# Charger.net
KiCad netlist of a schematic drawn in Altium Designer
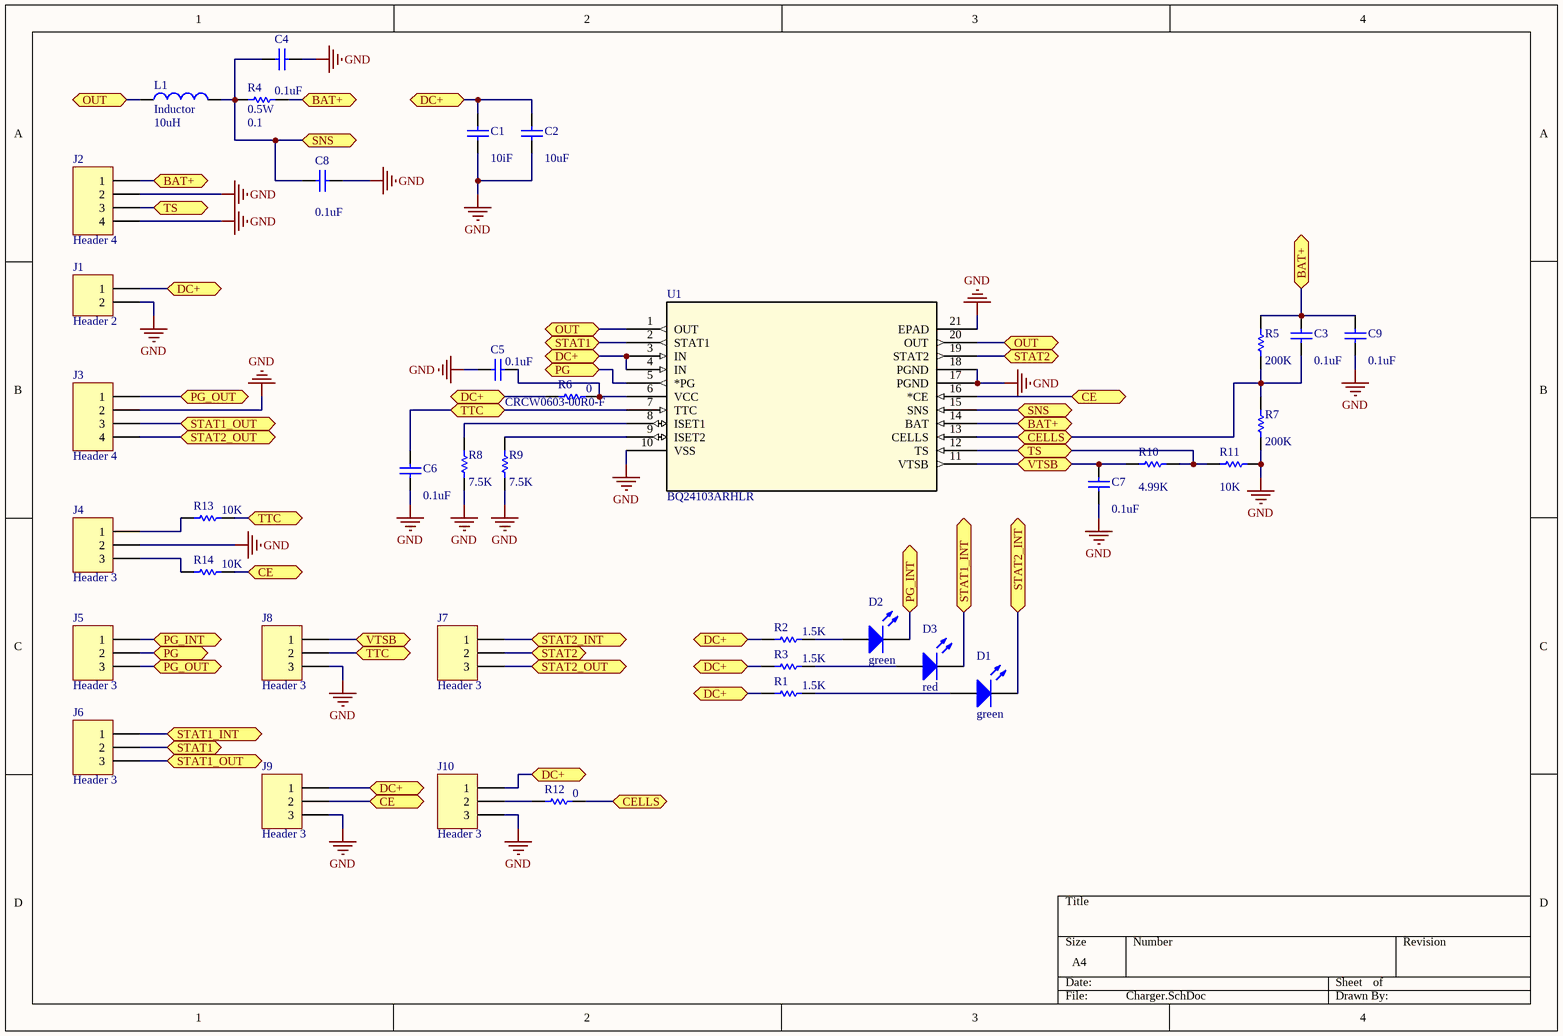
[diagram p0: Charger.SchDoc]

(export (version "E")
  (design (tool "Eeschema 10.0.6"))
  (components
    (comp (ref "C1")
      (value "10iF")
      (footprint "CAPC3216L")
      (description "Capacitor")
      (fields (field (name "PUBLISHER") "Altium Limited"))
      (libsource (lib "Miscellaneous Devices") (part "Cap"))
    )
    (comp (ref "C2")
      (value "10uF")
      (footprint "CAPC3216L")
      (description "Capacitor")
      (fields (field (name "PUBLISHER") "Altium Limited"))
      (libsource (lib "Miscellaneous Devices") (part "Cap"))
    )
    (comp (ref "C3")
      (value "0.1uF")
      (footprint "6-0805_L")
      (description "Capacitor")
      (fields (field (name "PUBLISHER") "Altium Limited"))
      (libsource (lib "Miscellaneous Devices") (part "Cap"))
    )
    (comp (ref "C4")
      (value "0.1uF")
      (footprint "CAPC3216L")
      (description "Capacitor")
      (fields (field (name "PUBLISHER") "Altium Limited"))
      (libsource (lib "Miscellaneous Devices") (part "Cap"))
    )
    (comp (ref "C5")
      (value "0.1uF")
      (footprint "6-0805_L")
      (description "Capacitor")
      (fields (field (name "PUBLISHER") "Altium Limited"))
      (libsource (lib "Miscellaneous Devices") (part "Cap"))
    )
    (comp (ref "C6")
      (value "0.1uF")
      (footprint "6-0805_L")
      (description "Capacitor")
      (fields (field (name "PUBLISHER") "Altium Limited"))
      (libsource (lib "Miscellaneous Devices") (part "Cap"))
    )
    (comp (ref "C7")
      (value "0.1uF")
      (footprint "6-0805_L")
      (description "Capacitor")
      (fields (field (name "PUBLISHER") "Altium Limited"))
      (libsource (lib "Miscellaneous Devices") (part "Cap"))
    )
    (comp (ref "C8")
      (value "0.1uF")
      (footprint "6-0805_L")
      (description "Capacitor")
      (fields (field (name "PUBLISHER") "Altium Limited"))
      (libsource (lib "Miscellaneous Devices") (part "Cap"))
    )
    (comp (ref "C9")
      (value "0.1uF")
      (footprint "CAPC3216L")
      (description "Capacitor")
      (fields (field (name "PUBLISHER") "Altium Limited"))
      (libsource (lib "Miscellaneous Devices") (part "Cap"))
    )
    (comp (ref "D1")
      (value "green")
      (footprint "6-0805_L")
      (description "Typical RED, GREEN, YELLOW, AMBER GaAs LED")
      (fields (field (name "PUBLISHER") "Altium Limited"))
      (libsource (lib "Miscellaneous Devices") (part "LED2"))
    )
    (comp (ref "D2")
      (value "green")
      (footprint "6-0805_L")
      (description "Typical RED, GREEN, YELLOW, AMBER GaAs LED")
      (fields (field (name "PUBLISHER") "Altium Limited"))
      (libsource (lib "Miscellaneous Devices") (part "LED2"))
    )
    (comp (ref "D3")
      (value "red")
      (footprint "6-0805_L")
      (description "Typical RED, GREEN, YELLOW, AMBER GaAs LED")
      (fields (field (name "PUBLISHER") "Altium Limited"))
      (libsource (lib "Miscellaneous Devices") (part "LED2"))
    )
    (comp (ref "J1")
      (value "Header 2")
      (footprint "691305130002")
      (description "Header, 2-Pin")
      (fields (field (name "PUBLISHER") "Altium Limited"))
      (libsource (lib "Miscellaneous Connectors") (part "Header 2"))
    )
    (comp (ref "J2")
      (value "Header 4")
      (footprint "691305130004")
      (description "Header, 4-Pin")
      (fields (field (name "PUBLISHER") "Altium Limited"))
      (libsource (lib "Miscellaneous Connectors") (part "Header 4"))
    )
    (comp (ref "J3")
      (value "Header 4")
      (footprint "691305130004")
      (description "Header, 4-Pin")
      (fields (field (name "PUBLISHER") "Altium Limited"))
      (libsource (lib "Miscellaneous Connectors") (part "Header 4"))
    )
    (comp (ref "J4")
      (value "Header 3")
      (footprint "691305130003")
      (description "Header, 3-Pin")
      (fields (field (name "PUBLISHER") "Altium Limited"))
      (libsource (lib "Miscellaneous Connectors") (part "Header 3"))
    )
    (comp (ref "J5")
      (value "Header 3")
      (footprint "HDR1X3")
      (description "Header, 3-Pin")
      (fields (field (name "PUBLISHER") "Altium Limited"))
      (libsource (lib "Miscellaneous Connectors") (part "Header 3"))
    )
    (comp (ref "J6")
      (value "Header 3")
      (footprint "HDR1X3")
      (description "Header, 3-Pin")
      (fields (field (name "PUBLISHER") "Altium Limited"))
      (libsource (lib "Miscellaneous Connectors") (part "Header 3"))
    )
    (comp (ref "J7")
      (value "Header 3")
      (footprint "HDR1X3")
      (description "Header, 3-Pin")
      (fields (field (name "PUBLISHER") "Altium Limited"))
      (libsource (lib "Miscellaneous Connectors") (part "Header 3"))
    )
    (comp (ref "J8")
      (value "Header 3")
      (footprint "HDR1X3")
      (description "Header, 3-Pin")
      (fields (field (name "PUBLISHER") "Altium Limited"))
      (libsource (lib "Miscellaneous Connectors") (part "Header 3"))
    )
    (comp (ref "J9")
      (value "Header 3")
      (footprint "HDR1X3")
      (description "Header, 3-Pin")
      (fields (field (name "PUBLISHER") "Altium Limited"))
      (libsource (lib "Miscellaneous Connectors") (part "Header 3"))
    )
    (comp (ref "J10")
      (value "Header 3")
      (footprint "HDR1X3")
      (description "Header, 3-Pin")
      (fields (field (name "PUBLISHER") "Altium Limited"))
      (libsource (lib "Miscellaneous Connectors") (part "Header 3"))
    )
    (comp (ref "L1")
      (value "Inductor")
      (footprint "IND2926")
      (fields (field (name "ALTIUM_VALUE") "10uH") (field (name "PUBLISHER") "Altium Limited"))
      (libsource (lib "Miscellaneous Devices") (part "Inductor"))
    )
    (comp (ref "R1")
      (value "1.5K")
      (footprint "6-0805_L")
      (description "Resistor")
      (fields (field (name "PUBLISHER") "Altium Limited"))
      (libsource (lib "Miscellaneous Devices") (part "Res1"))
    )
    (comp (ref "R2")
      (value "1.5K")
      (footprint "6-0805_L")
      (description "Resistor")
      (fields (field (name "PUBLISHER") "Altium Limited"))
      (libsource (lib "Miscellaneous Devices") (part "Res1"))
    )
    (comp (ref "R3")
      (value "1.5K")
      (footprint "6-0805_L")
      (description "Resistor")
      (fields (field (name "PUBLISHER") "Altium Limited"))
      (libsource (lib "Miscellaneous Devices") (part "Res1"))
    )
    (comp (ref "R4")
      (value "0.5W")
      (footprint "12Z-2010")
      (description "Resistor")
      (fields (field (name "ALTIUM_VALUE") "0.1") (field (name "PUBLISHER") "Altium Limited"))
      (libsource (lib "Miscellaneous Devices") (part "Res1"))
    )
    (comp (ref "R5")
      (value "200K")
      (footprint "6-0805_L")
      (description "Resistor")
      (fields (field (name "PUBLISHER") "Altium Limited"))
      (libsource (lib "Miscellaneous Devices") (part "Res1"))
    )
    (comp (ref "R6")
      (value "CRCW0603-00R0-F")
      (footprint "6-0805_L")
      (description "Resistor")
      (fields (field (name "ALTIUM_VALUE") "0") (field (name "PUBLISHER") "Altium Limited"))
      (libsource (lib "Miscellaneous Devices") (part "Res1"))
    )
    (comp (ref "R7")
      (value "200K")
      (footprint "6-0805_L")
      (description "Resistor")
      (fields (field (name "PUBLISHER") "Altium Limited"))
      (libsource (lib "Miscellaneous Devices") (part "Res1"))
    )
    (comp (ref "R8")
      (value "7.5K")
      (footprint "6-0805_L")
      (description "Resistor")
      (fields (field (name "PUBLISHER") "Altium Limited"))
      (libsource (lib "Miscellaneous Devices") (part "Res1"))
    )
    (comp (ref "R9")
      (value "7.5K")
      (footprint "6-0805_L")
      (description "Resistor")
      (fields (field (name "PUBLISHER") "Altium Limited"))
      (libsource (lib "Miscellaneous Devices") (part "Res1"))
    )
    (comp (ref "R10")
      (value "4.99K")
      (footprint "6-0805_L")
      (description "Resistor")
      (fields (field (name "PUBLISHER") "Altium Limited"))
      (libsource (lib "Miscellaneous Devices") (part "Res1"))
    )
    (comp (ref "R11")
      (value "10K")
      (footprint "6-0805_L")
      (description "Resistor")
      (fields (field (name "PUBLISHER") "Altium Limited"))
      (libsource (lib "Miscellaneous Devices") (part "Res1"))
    )
    (comp (ref "R12")
      (value "0")
      (footprint "6-0805_L")
      (description "Resistor")
      (fields (field (name "PUBLISHER") "Altium Limited"))
      (libsource (lib "Miscellaneous Devices") (part "Res1"))
    )
    (comp (ref "R13")
      (value "10K")
      (footprint "6-0805_L")
      (description "Resistor")
      (fields (field (name "PUBLISHER") "Altium Limited"))
      (libsource (lib "Miscellaneous Devices") (part "Res1"))
    )
    (comp (ref "R14")
      (value "10K")
      (footprint "6-0805_L")
      (description "Resistor")
      (fields (field (name "PUBLISHER") "Altium Limited"))
      (libsource (lib "Miscellaneous Devices") (part "Res1"))
    )
    (comp (ref "U1")
      (value "BQ24103ARHLR")
      (footprint "RHL20_2P05X3P05")
      (description "Imported")
      (fields
        (field (name "MANUFACTURER") "Texas Instruments")
        (field (name "GENERIC_PART_NUMBER") "BQ24103A")
        (field (name "COPYRIGHT") "Copyright (C) 2015 Accelerated Designs. All rights reserved")
      )
      (libsource (lib "bq24103") (part "BQ24103ARHLR"))
    )
  )
  (nets
    (net (code "1") (name "/BAT+") (class "Default")
      (node (ref "C3") (pin "1") (pinfunction "1_1") (pintype "passive"))
      (node (ref "C9") (pin "1") (pinfunction "1_1") (pintype "passive"))
      (node (ref "J2") (pin "1") (pinfunction "1_1") (pintype "passive"))
      (node (ref "R4") (pin "2") (pinfunction "2_2") (pintype "passive"))
      (node (ref "R5") (pin "1") (pinfunction "1_1") (pintype "passive"))
      (node (ref "U1") (pin "14") (pinfunction "BAT_14") (pintype "input"))
    )
    (net (code "2") (name "/CE") (class "Default")
      (node (ref "J9") (pin "2") (pinfunction "2_2") (pintype "passive"))
      (node (ref "R14") (pin "2") (pinfunction "2_2") (pintype "passive"))
      (node (ref "U1") (pin "16") (pinfunction "*CE_16") (pintype "input"))
    )
    (net (code "3") (name "/CELLS") (class "Default")
      (node (ref "C3") (pin "2") (pinfunction "2_2") (pintype "passive"))
      (node (ref "R12") (pin "2") (pinfunction "2_2") (pintype "passive"))
      (node (ref "R5") (pin "2") (pinfunction "2_2") (pintype "passive"))
      (node (ref "R7") (pin "1") (pinfunction "1_1") (pintype "passive"))
      (node (ref "U1") (pin "13") (pinfunction "CELLS_13") (pintype "input"))
    )
    (net (code "4") (name "/DC+") (class "Default")
      (node (ref "C1") (pin "2") (pinfunction "2_2") (pintype "passive"))
      (node (ref "C2") (pin "2") (pinfunction "2_2") (pintype "passive"))
      (node (ref "J1") (pin "1") (pinfunction "1_1") (pintype "passive"))
      (node (ref "J10") (pin "1") (pinfunction "1_1") (pintype "passive"))
      (node (ref "J9") (pin "1") (pinfunction "1_1") (pintype "passive"))
      (node (ref "R1") (pin "1") (pinfunction "1_1") (pintype "passive"))
      (node (ref "R2") (pin "1") (pinfunction "1_1") (pintype "passive"))
      (node (ref "R3") (pin "1") (pinfunction "1_1") (pintype "passive"))
      (node (ref "R6") (pin "1") (pinfunction "1_1") (pintype "passive"))
      (node (ref "U1") (pin "3") (pinfunction "IN_3") (pintype "input"))
      (node (ref "U1") (pin "4") (pinfunction "IN_4") (pintype "input"))
    )
    (net (code "5") (name "/OUT") (class "Default")
      (node (ref "L1") (pin "1") (pinfunction "1_1") (pintype "passive"))
      (node (ref "U1") (pin "1") (pinfunction "OUT_1") (pintype "output"))
      (node (ref "U1") (pin "20") (pinfunction "OUT_20") (pintype "output"))
    )
    (net (code "6") (name "/PG") (class "Default")
      (node (ref "J5") (pin "2") (pinfunction "2_2") (pintype "passive"))
      (node (ref "U1") (pin "5") (pinfunction "*PG_5") (pintype "output"))
    )
    (net (code "7") (name "/PG_INT") (class "Default")
      (node (ref "D2") (pin "2") (pinfunction "K_2") (pintype "passive"))
      (node (ref "J5") (pin "1") (pinfunction "1_1") (pintype "passive"))
    )
    (net (code "8") (name "/PG_OUT") (class "Default")
      (node (ref "J3") (pin "1") (pinfunction "1_1") (pintype "passive"))
      (node (ref "J5") (pin "3") (pinfunction "3_3") (pintype "passive"))
    )
    (net (code "9") (name "/SNS") (class "Default")
      (node (ref "C4") (pin "1") (pinfunction "1_1") (pintype "passive"))
      (node (ref "C8") (pin "1") (pinfunction "1_1") (pintype "passive"))
      (node (ref "L1") (pin "2") (pinfunction "2_2") (pintype "passive"))
      (node (ref "R4") (pin "1") (pinfunction "1_1") (pintype "passive"))
      (node (ref "U1") (pin "15") (pinfunction "SNS_15") (pintype "input"))
    )
    (net (code "10") (name "/STAT1") (class "Default")
      (node (ref "J6") (pin "2") (pinfunction "2_2") (pintype "passive"))
      (node (ref "U1") (pin "2") (pinfunction "STAT1_2") (pintype "output"))
    )
    (net (code "11") (name "/STAT1_INT") (class "Default")
      (node (ref "D3") (pin "2") (pinfunction "K_2") (pintype "passive"))
      (node (ref "J6") (pin "1") (pinfunction "1_1") (pintype "passive"))
    )
    (net (code "12") (name "/STAT1_OUT") (class "Default")
      (node (ref "J3") (pin "3") (pinfunction "3_3") (pintype "passive"))
      (node (ref "J6") (pin "3") (pinfunction "3_3") (pintype "passive"))
    )
    (net (code "13") (name "/STAT2") (class "Default")
      (node (ref "J7") (pin "2") (pinfunction "2_2") (pintype "passive"))
      (node (ref "U1") (pin "19") (pinfunction "STAT2_19") (pintype "output"))
    )
    (net (code "14") (name "/STAT2_INT") (class "Default")
      (node (ref "D1") (pin "2") (pinfunction "K_2") (pintype "passive"))
      (node (ref "J7") (pin "1") (pinfunction "1_1") (pintype "passive"))
    )
    (net (code "15") (name "/STAT2_OUT") (class "Default")
      (node (ref "J3") (pin "4") (pinfunction "4_4") (pintype "passive"))
      (node (ref "J7") (pin "3") (pinfunction "3_3") (pintype "passive"))
    )
    (net (code "16") (name "/TS") (class "Default")
      (node (ref "J2") (pin "3") (pinfunction "3_3") (pintype "passive"))
      (node (ref "R10") (pin "1") (pinfunction "1_1") (pintype "passive"))
      (node (ref "R11") (pin "2") (pinfunction "2_2") (pintype "passive"))
      (node (ref "U1") (pin "12") (pinfunction "TS_12") (pintype "input"))
    )
    (net (code "17") (name "/TTC") (class "Default")
      (node (ref "C6") (pin "1") (pinfunction "1_1") (pintype "passive"))
      (node (ref "J8") (pin "2") (pinfunction "2_2") (pintype "passive"))
      (node (ref "R13") (pin "2") (pinfunction "2_2") (pintype "passive"))
      (node (ref "U1") (pin "7") (pinfunction "TTC_7") (pintype "input"))
    )
    (net (code "18") (name "/VTSB") (class "Default")
      (node (ref "C7") (pin "1") (pinfunction "1_1") (pintype "passive"))
      (node (ref "J8") (pin "1") (pinfunction "1_1") (pintype "passive"))
      (node (ref "R10") (pin "2") (pinfunction "2_2") (pintype "passive"))
      (node (ref "U1") (pin "11") (pinfunction "VTSB_11") (pintype "output"))
    )
    (net (code "19") (name "GND") (class "Default")
      (node (ref "C1") (pin "1") (pinfunction "1_1") (pintype "passive"))
      (node (ref "C2") (pin "1") (pinfunction "1_1") (pintype "passive"))
      (node (ref "C4") (pin "2") (pinfunction "2_2") (pintype "passive"))
      (node (ref "C5") (pin "2") (pinfunction "2_2") (pintype "passive"))
      (node (ref "C6") (pin "2") (pinfunction "2_2") (pintype "passive"))
      (node (ref "C7") (pin "2") (pinfunction "2_2") (pintype "passive"))
      (node (ref "C8") (pin "2") (pinfunction "2_2") (pintype "passive"))
      (node (ref "C9") (pin "2") (pinfunction "2_2") (pintype "passive"))
      (node (ref "J1") (pin "2") (pinfunction "2_2") (pintype "passive"))
      (node (ref "J10") (pin "3") (pinfunction "3_3") (pintype "passive"))
      (node (ref "J2") (pin "2") (pinfunction "2_2") (pintype "passive"))
      (node (ref "J2") (pin "4") (pinfunction "4_4") (pintype "passive"))
      (node (ref "J3") (pin "2") (pinfunction "2_2") (pintype "passive"))
      (node (ref "J4") (pin "2") (pinfunction "2_2") (pintype "passive"))
      (node (ref "J8") (pin "3") (pinfunction "3_3") (pintype "passive"))
      (node (ref "J9") (pin "3") (pinfunction "3_3") (pintype "passive"))
      (node (ref "R11") (pin "1") (pinfunction "1_1") (pintype "passive"))
      (node (ref "R7") (pin "2") (pinfunction "2_2") (pintype "passive"))
      (node (ref "R8") (pin "1") (pinfunction "1_1") (pintype "passive"))
      (node (ref "R9") (pin "1") (pinfunction "1_1") (pintype "passive"))
      (node (ref "U1") (pin "10") (pinfunction "VSS_10") (pintype "power_in"))
      (node (ref "U1") (pin "17") (pinfunction "PGND_17") (pintype "power_in"))
      (node (ref "U1") (pin "18") (pinfunction "PGND_18") (pintype "power_in"))
      (node (ref "U1") (pin "21") (pinfunction "EPAD_21") (pintype "passive"))
    )
    (net (code "20") (name "Net-(D1-A)") (class "Default")
      (node (ref "D1") (pin "1") (pinfunction "A_1") (pintype "passive"))
      (node (ref "R1") (pin "2") (pinfunction "2_2") (pintype "passive"))
    )
    (net (code "21") (name "Net-(D2-A)") (class "Default")
      (node (ref "D2") (pin "1") (pinfunction "A_1") (pintype "passive"))
      (node (ref "R2") (pin "2") (pinfunction "2_2") (pintype "passive"))
    )
    (net (code "22") (name "Net-(D3-A)") (class "Default")
      (node (ref "D3") (pin "1") (pinfunction "A_1") (pintype "passive"))
      (node (ref "R3") (pin "2") (pinfunction "2_2") (pintype "passive"))
    )
    (net (code "23") (name "Net-(J4-Pad1)") (class "Default")
      (node (ref "J4") (pin "1") (pinfunction "1_1") (pintype "passive"))
      (node (ref "R13") (pin "1") (pinfunction "1_1") (pintype "passive"))
    )
    (net (code "24") (name "Net-(J4-Pad3)") (class "Default")
      (node (ref "J4") (pin "3") (pinfunction "3_3") (pintype "passive"))
      (node (ref "R14") (pin "1") (pinfunction "1_1") (pintype "passive"))
    )
    (net (code "25") (name "Net-(J10-Pad2)") (class "Default")
      (node (ref "J10") (pin "2") (pinfunction "2_2") (pintype "passive"))
      (node (ref "R12") (pin "1") (pinfunction "1_1") (pintype "passive"))
    )
    (net (code "26") (name "Net-(U1-ISET1)") (class "Default")
      (node (ref "R8") (pin "2") (pinfunction "2_2") (pintype "passive"))
      (node (ref "U1") (pin "8") (pinfunction "ISET1_8") (pintype "bidirectional"))
    )
    (net (code "27") (name "Net-(U1-ISET2)") (class "Default")
      (node (ref "R9") (pin "2") (pinfunction "2_2") (pintype "passive"))
      (node (ref "U1") (pin "9") (pinfunction "ISET2_9") (pintype "bidirectional"))
    )
    (net (code "28") (name "Net-(U1-VCC)") (class "Default")
      (node (ref "C5") (pin "1") (pinfunction "1_1") (pintype "passive"))
      (node (ref "R6") (pin "2") (pinfunction "2_2") (pintype "passive"))
      (node (ref "U1") (pin "6") (pinfunction "VCC_6") (pintype "power_in"))
    )
  )
)
